# arduino_adapter_2a.net
KiCad netlist of a schematic drawn in EAGLE
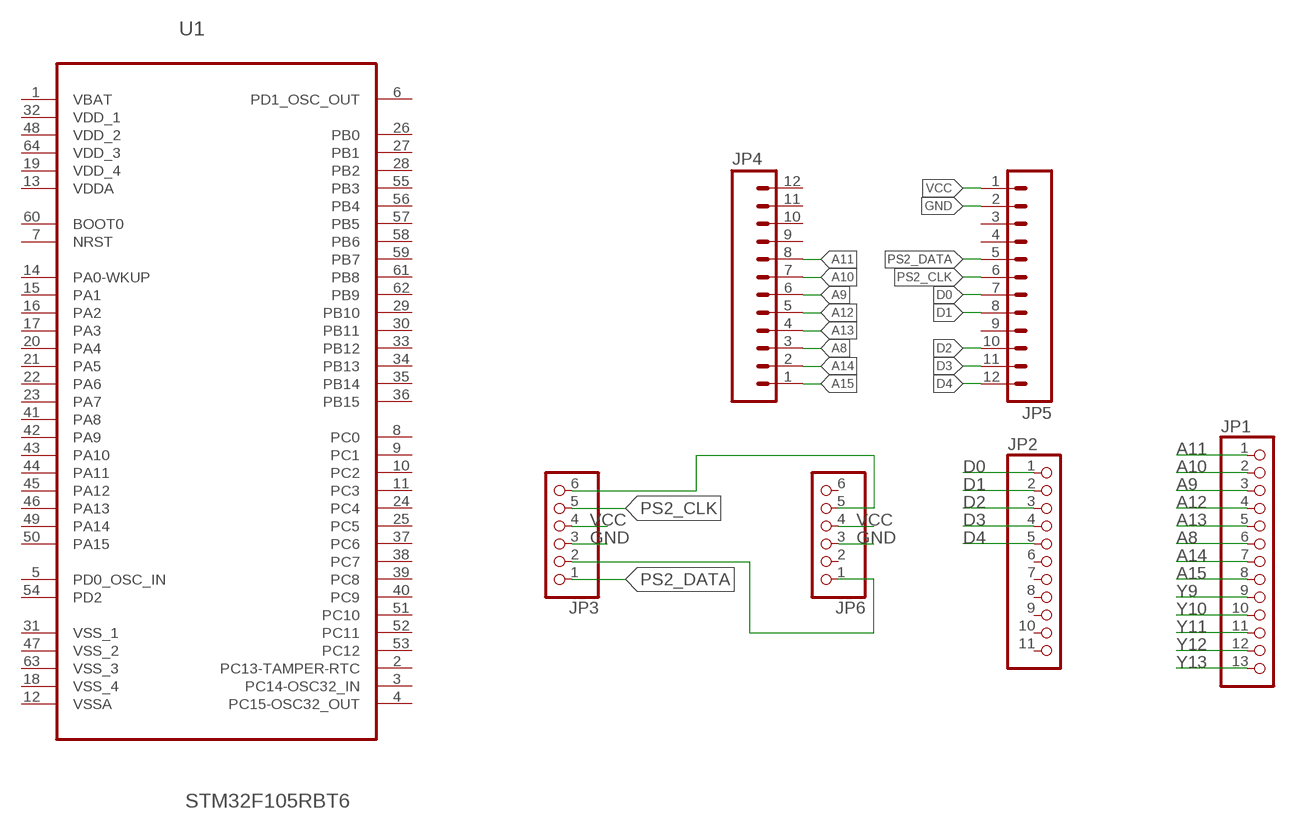
[diagram p0: schematic, sheet 1]

(export (version "E")
  (design (tool "Eeschema 10.0.6"))
  (components
    (comp (ref "JP1")
      (value "PINHD-1X13")
      (footprint "eagle-import:1X13")
      (libsource (lib "eagle-import") (part "PINHD-1X13"))
    )
    (comp (ref "JP2")
      (value "PINHD-1X11")
      (footprint "eagle-import:1X11")
      (libsource (lib "eagle-import") (part "PINHD-1X11"))
    )
    (comp (ref "JP3")
      (value "PINHD-1X6")
      (footprint "eagle-import:1X06")
      (libsource (lib "eagle-import") (part "PINHD-1X6"))
    )
    (comp (ref "JP4")
      (value "M12PTH")
      (footprint "eagle-import:1X12")
      (libsource (lib "eagle-import") (part "M12PTH"))
    )
    (comp (ref "JP5")
      (value "M12PTH")
      (footprint "eagle-import:1X12")
      (libsource (lib "eagle-import") (part "M12PTH"))
    )
    (comp (ref "JP6")
      (value "PINHD-1X6")
      (footprint "eagle-import:1X06")
      (libsource (lib "eagle-import") (part "PINHD-1X6"))
    )
    (comp (ref "U1")
      (value "STM32F105RBT6")
      (footprint "eagle-import:QFP50P1200X1200X160-64N")
      (libsource (lib "eagle-import") (part "STM32F105RBT6"))
    )
  )
  (nets
    (net (code "1") (name "/VBAT") (class "Default")
      (node (ref "U1") (pin "1") (pinfunction "VBAT_1") (pintype "power_in"))
    )
    (net (code "2") (name "/VDDA") (class "Default")
      (node (ref "U1") (pin "13") (pinfunction "VDDA_13") (pintype "power_in"))
    )
    (net (code "3") (name "/VDD_1") (class "Default")
      (node (ref "U1") (pin "32") (pinfunction "VDD_1_32") (pintype "power_in"))
    )
    (net (code "4") (name "/VDD_2") (class "Default")
      (node (ref "U1") (pin "48") (pinfunction "VDD_2_48") (pintype "power_in"))
    )
    (net (code "5") (name "/VDD_3") (class "Default")
      (node (ref "U1") (pin "64") (pinfunction "VDD_3_64") (pintype "power_in"))
    )
    (net (code "6") (name "/VDD_4") (class "Default")
      (node (ref "U1") (pin "19") (pinfunction "VDD_4_19") (pintype "power_in"))
    )
    (net (code "7") (name "/VSSA") (class "Default")
      (node (ref "U1") (pin "12") (pinfunction "VSSA_12") (pintype "power_in"))
    )
    (net (code "8") (name "/VSS_1") (class "Default")
      (node (ref "U1") (pin "31") (pinfunction "VSS_1_31") (pintype "power_in"))
    )
    (net (code "9") (name "/VSS_2") (class "Default")
      (node (ref "U1") (pin "47") (pinfunction "VSS_2_47") (pintype "power_in"))
    )
    (net (code "10") (name "/VSS_3") (class "Default")
      (node (ref "U1") (pin "63") (pinfunction "VSS_3_63") (pintype "power_in"))
    )
    (net (code "11") (name "/VSS_4") (class "Default")
      (node (ref "U1") (pin "18") (pinfunction "VSS_4_18") (pintype "power_in"))
    )
    (net (code "12") (name "/Y9") (class "Default")
      (node (ref "JP1") (pin "9") (pinfunction "9_9") (pintype "passive"))
    )
    (net (code "13") (name "/Y10") (class "Default")
      (node (ref "JP1") (pin "10") (pinfunction "10_10") (pintype "passive"))
    )
    (net (code "14") (name "/Y11") (class "Default")
      (node (ref "JP1") (pin "11") (pinfunction "11_11") (pintype "passive"))
    )
    (net (code "15") (name "/Y12") (class "Default")
      (node (ref "JP1") (pin "12") (pinfunction "12_12") (pintype "passive"))
    )
    (net (code "16") (name "/Y13") (class "Default")
      (node (ref "JP1") (pin "13") (pinfunction "13_13") (pintype "passive"))
    )
    (net (code "17") (name "A8") (class "Default")
      (node (ref "JP1") (pin "6") (pinfunction "6_6") (pintype "passive"))
      (node (ref "JP4") (pin "3") (pinfunction "3_3") (pintype "passive"))
    )
    (net (code "18") (name "A9") (class "Default")
      (node (ref "JP1") (pin "3") (pinfunction "3_3") (pintype "passive"))
      (node (ref "JP4") (pin "6") (pinfunction "6_6") (pintype "passive"))
    )
    (net (code "19") (name "A10") (class "Default")
      (node (ref "JP1") (pin "2") (pinfunction "2_2") (pintype "passive"))
      (node (ref "JP4") (pin "7") (pinfunction "7_7") (pintype "passive"))
    )
    (net (code "20") (name "A11") (class "Default")
      (node (ref "JP1") (pin "1") (pinfunction "1_1") (pintype "passive"))
      (node (ref "JP4") (pin "8") (pinfunction "8_8") (pintype "passive"))
    )
    (net (code "21") (name "A12") (class "Default")
      (node (ref "JP1") (pin "4") (pinfunction "4_4") (pintype "passive"))
      (node (ref "JP4") (pin "5") (pinfunction "5_5") (pintype "passive"))
    )
    (net (code "22") (name "A13") (class "Default")
      (node (ref "JP1") (pin "5") (pinfunction "5_5") (pintype "passive"))
      (node (ref "JP4") (pin "4") (pinfunction "4_4") (pintype "passive"))
    )
    (net (code "23") (name "A14") (class "Default")
      (node (ref "JP1") (pin "7") (pinfunction "7_7") (pintype "passive"))
      (node (ref "JP4") (pin "2") (pinfunction "2_2") (pintype "passive"))
    )
    (net (code "24") (name "A15") (class "Default")
      (node (ref "JP1") (pin "8") (pinfunction "8_8") (pintype "passive"))
      (node (ref "JP4") (pin "1") (pinfunction "1_1") (pintype "passive"))
    )
    (net (code "25") (name "D0") (class "Default")
      (node (ref "JP2") (pin "1") (pinfunction "1_1") (pintype "passive"))
      (node (ref "JP5") (pin "7") (pinfunction "7_7") (pintype "passive"))
    )
    (net (code "26") (name "D1") (class "Default")
      (node (ref "JP2") (pin "2") (pinfunction "2_2") (pintype "passive"))
      (node (ref "JP5") (pin "8") (pinfunction "8_8") (pintype "passive"))
    )
    (net (code "27") (name "D2") (class "Default")
      (node (ref "JP2") (pin "3") (pinfunction "3_3") (pintype "passive"))
      (node (ref "JP5") (pin "10") (pinfunction "10_10") (pintype "passive"))
    )
    (net (code "28") (name "D3") (class "Default")
      (node (ref "JP2") (pin "4") (pinfunction "4_4") (pintype "passive"))
      (node (ref "JP5") (pin "11") (pinfunction "11_11") (pintype "passive"))
    )
    (net (code "29") (name "D4") (class "Default")
      (node (ref "JP2") (pin "5") (pinfunction "5_5") (pintype "passive"))
      (node (ref "JP5") (pin "12") (pinfunction "12_12") (pintype "passive"))
    )
    (net (code "30") (name "GND") (class "Default")
      (node (ref "JP3") (pin "3") (pinfunction "3_3") (pintype "passive"))
      (node (ref "JP5") (pin "2") (pinfunction "2_2") (pintype "passive"))
      (node (ref "JP6") (pin "3") (pinfunction "3_3") (pintype "passive"))
    )
    (net (code "31") (name "Net-(JP3-Pad2)") (class "Default")
      (node (ref "JP3") (pin "2") (pinfunction "2_2") (pintype "passive"))
      (node (ref "JP6") (pin "1") (pinfunction "1_1") (pintype "passive"))
    )
    (net (code "32") (name "Net-(JP3-Pad6)") (class "Default")
      (node (ref "JP3") (pin "6") (pinfunction "6_6") (pintype "passive"))
      (node (ref "JP6") (pin "5") (pinfunction "5_5") (pintype "passive"))
    )
    (net (code "33") (name "PS2_CLK") (class "Default")
      (node (ref "JP3") (pin "5") (pinfunction "5_5") (pintype "passive"))
      (node (ref "JP5") (pin "6") (pinfunction "6_6") (pintype "passive"))
    )
    (net (code "34") (name "PS2_DATA") (class "Default")
      (node (ref "JP3") (pin "1") (pinfunction "1_1") (pintype "passive"))
      (node (ref "JP5") (pin "5") (pinfunction "5_5") (pintype "passive"))
    )
    (net (code "35") (name "VCC") (class "Default")
      (node (ref "JP3") (pin "4") (pinfunction "4_4") (pintype "passive"))
      (node (ref "JP5") (pin "1") (pinfunction "1_1") (pintype "passive"))
      (node (ref "JP6") (pin "4") (pinfunction "4_4") (pintype "passive"))
    )
    (net (code "36") (name "unconnected-(JP2-Pad6)") (class "Default")
      (node (ref "JP2") (pin "6") (pinfunction "6_6") (pintype "passive"))
    )
    (net (code "37") (name "unconnected-(JP2-Pad7)") (class "Default")
      (node (ref "JP2") (pin "7") (pinfunction "7_7") (pintype "passive"))
    )
    (net (code "38") (name "unconnected-(JP2-Pad8)") (class "Default")
      (node (ref "JP2") (pin "8") (pinfunction "8_8") (pintype "passive"))
    )
    (net (code "39") (name "unconnected-(JP2-Pad9)") (class "Default")
      (node (ref "JP2") (pin "9") (pinfunction "9_9") (pintype "passive"))
    )
    (net (code "40") (name "unconnected-(JP2-Pad10)") (class "Default")
      (node (ref "JP2") (pin "10") (pinfunction "10_10") (pintype "passive"))
    )
    (net (code "41") (name "unconnected-(JP2-Pad11)") (class "Default")
      (node (ref "JP2") (pin "11") (pinfunction "11_11") (pintype "passive"))
    )
    (net (code "42") (name "unconnected-(JP4-Pad9)") (class "Default")
      (node (ref "JP4") (pin "9") (pinfunction "9_9") (pintype "passive"))
    )
    (net (code "43") (name "unconnected-(JP4-Pad10)") (class "Default")
      (node (ref "JP4") (pin "10") (pinfunction "10_10") (pintype "passive"))
    )
    (net (code "44") (name "unconnected-(JP4-Pad11)") (class "Default")
      (node (ref "JP4") (pin "11") (pinfunction "11_11") (pintype "passive"))
    )
    (net (code "45") (name "unconnected-(JP4-Pad12)") (class "Default")
      (node (ref "JP4") (pin "12") (pinfunction "12_12") (pintype "passive"))
    )
    (net (code "46") (name "unconnected-(JP5-Pad3)") (class "Default")
      (node (ref "JP5") (pin "3") (pinfunction "3_3") (pintype "passive"))
    )
    (net (code "47") (name "unconnected-(JP5-Pad4)") (class "Default")
      (node (ref "JP5") (pin "4") (pinfunction "4_4") (pintype "passive"))
    )
    (net (code "48") (name "unconnected-(JP5-Pad9)") (class "Default")
      (node (ref "JP5") (pin "9") (pinfunction "9_9") (pintype "passive"))
    )
    (net (code "49") (name "unconnected-(JP6-Pad2)") (class "Default")
      (node (ref "JP6") (pin "2") (pinfunction "2_2") (pintype "passive"))
    )
    (net (code "50") (name "unconnected-(JP6-Pad6)") (class "Default")
      (node (ref "JP6") (pin "6") (pinfunction "6_6") (pintype "passive"))
    )
    (net (code "51") (name "unconnected-(U1-BOOT0-Pad60)") (class "Default")
      (node (ref "U1") (pin "60") (pinfunction "BOOT0_60") (pintype "input"))
    )
    (net (code "52") (name "unconnected-(U1-NRST-Pad7)") (class "Default")
      (node (ref "U1") (pin "7") (pinfunction "NRST_7") (pintype "bidirectional"))
    )
    (net (code "53") (name "unconnected-(U1-PA0-WKUP-Pad14)") (class "Default")
      (node (ref "U1") (pin "14") (pinfunction "PA0-WKUP_14") (pintype "bidirectional"))
    )
    (net (code "54") (name "unconnected-(U1-PA1-Pad15)") (class "Default")
      (node (ref "U1") (pin "15") (pinfunction "PA1_15") (pintype "bidirectional"))
    )
    (net (code "55") (name "unconnected-(U1-PA2-Pad16)") (class "Default")
      (node (ref "U1") (pin "16") (pinfunction "PA2_16") (pintype "bidirectional"))
    )
    (net (code "56") (name "unconnected-(U1-PA3-Pad17)") (class "Default")
      (node (ref "U1") (pin "17") (pinfunction "PA3_17") (pintype "bidirectional"))
    )
    (net (code "57") (name "unconnected-(U1-PA4-Pad20)") (class "Default")
      (node (ref "U1") (pin "20") (pinfunction "PA4_20") (pintype "bidirectional"))
    )
    (net (code "58") (name "unconnected-(U1-PA5-Pad21)") (class "Default")
      (node (ref "U1") (pin "21") (pinfunction "PA5_21") (pintype "bidirectional"))
    )
    (net (code "59") (name "unconnected-(U1-PA6-Pad22)") (class "Default")
      (node (ref "U1") (pin "22") (pinfunction "PA6_22") (pintype "bidirectional"))
    )
    (net (code "60") (name "unconnected-(U1-PA7-Pad23)") (class "Default")
      (node (ref "U1") (pin "23") (pinfunction "PA7_23") (pintype "bidirectional"))
    )
    (net (code "61") (name "unconnected-(U1-PA8-Pad41)") (class "Default")
      (node (ref "U1") (pin "41") (pinfunction "PA8_41") (pintype "bidirectional"))
    )
    (net (code "62") (name "unconnected-(U1-PA9-Pad42)") (class "Default")
      (node (ref "U1") (pin "42") (pinfunction "PA9_42") (pintype "bidirectional"))
    )
    (net (code "63") (name "unconnected-(U1-PA10-Pad43)") (class "Default")
      (node (ref "U1") (pin "43") (pinfunction "PA10_43") (pintype "bidirectional"))
    )
    (net (code "64") (name "unconnected-(U1-PA11-Pad44)") (class "Default")
      (node (ref "U1") (pin "44") (pinfunction "PA11_44") (pintype "bidirectional"))
    )
    (net (code "65") (name "unconnected-(U1-PA12-Pad45)") (class "Default")
      (node (ref "U1") (pin "45") (pinfunction "PA12_45") (pintype "bidirectional"))
    )
    (net (code "66") (name "unconnected-(U1-PA13-Pad46)") (class "Default")
      (node (ref "U1") (pin "46") (pinfunction "PA13_46") (pintype "bidirectional"))
    )
    (net (code "67") (name "unconnected-(U1-PA14-Pad49)") (class "Default")
      (node (ref "U1") (pin "49") (pinfunction "PA14_49") (pintype "bidirectional"))
    )
    (net (code "68") (name "unconnected-(U1-PA15-Pad50)") (class "Default")
      (node (ref "U1") (pin "50") (pinfunction "PA15_50") (pintype "bidirectional"))
    )
    (net (code "69") (name "unconnected-(U1-PB0-Pad26)") (class "Default")
      (node (ref "U1") (pin "26") (pinfunction "PB0_26") (pintype "bidirectional"))
    )
    (net (code "70") (name "unconnected-(U1-PB1-Pad27)") (class "Default")
      (node (ref "U1") (pin "27") (pinfunction "PB1_27") (pintype "bidirectional"))
    )
    (net (code "71") (name "unconnected-(U1-PB2-Pad28)") (class "Default")
      (node (ref "U1") (pin "28") (pinfunction "PB2_28") (pintype "bidirectional"))
    )
    (net (code "72") (name "unconnected-(U1-PB3-Pad55)") (class "Default")
      (node (ref "U1") (pin "55") (pinfunction "PB3_55") (pintype "bidirectional"))
    )
    (net (code "73") (name "unconnected-(U1-PB4-Pad56)") (class "Default")
      (node (ref "U1") (pin "56") (pinfunction "PB4_56") (pintype "bidirectional"))
    )
    (net (code "74") (name "unconnected-(U1-PB5-Pad57)") (class "Default")
      (node (ref "U1") (pin "57") (pinfunction "PB5_57") (pintype "bidirectional"))
    )
    (net (code "75") (name "unconnected-(U1-PB6-Pad58)") (class "Default")
      (node (ref "U1") (pin "58") (pinfunction "PB6_58") (pintype "bidirectional"))
    )
    (net (code "76") (name "unconnected-(U1-PB7-Pad59)") (class "Default")
      (node (ref "U1") (pin "59") (pinfunction "PB7_59") (pintype "bidirectional"))
    )
    (net (code "77") (name "unconnected-(U1-PB8-Pad61)") (class "Default")
      (node (ref "U1") (pin "61") (pinfunction "PB8_61") (pintype "bidirectional"))
    )
    (net (code "78") (name "unconnected-(U1-PB9-Pad62)") (class "Default")
      (node (ref "U1") (pin "62") (pinfunction "PB9_62") (pintype "bidirectional"))
    )
    (net (code "79") (name "unconnected-(U1-PB10-Pad29)") (class "Default")
      (node (ref "U1") (pin "29") (pinfunction "PB10_29") (pintype "bidirectional"))
    )
    (net (code "80") (name "unconnected-(U1-PB11-Pad30)") (class "Default")
      (node (ref "U1") (pin "30") (pinfunction "PB11_30") (pintype "bidirectional"))
    )
    (net (code "81") (name "unconnected-(U1-PB12-Pad33)") (class "Default")
      (node (ref "U1") (pin "33") (pinfunction "PB12_33") (pintype "bidirectional"))
    )
    (net (code "82") (name "unconnected-(U1-PB13-Pad34)") (class "Default")
      (node (ref "U1") (pin "34") (pinfunction "PB13_34") (pintype "bidirectional"))
    )
    (net (code "83") (name "unconnected-(U1-PB14-Pad35)") (class "Default")
      (node (ref "U1") (pin "35") (pinfunction "PB14_35") (pintype "bidirectional"))
    )
    (net (code "84") (name "unconnected-(U1-PB15-Pad36)") (class "Default")
      (node (ref "U1") (pin "36") (pinfunction "PB15_36") (pintype "bidirectional"))
    )
    (net (code "85") (name "unconnected-(U1-PC0-Pad8)") (class "Default")
      (node (ref "U1") (pin "8") (pinfunction "PC0_8") (pintype "bidirectional"))
    )
    (net (code "86") (name "unconnected-(U1-PC1-Pad9)") (class "Default")
      (node (ref "U1") (pin "9") (pinfunction "PC1_9") (pintype "bidirectional"))
    )
    (net (code "87") (name "unconnected-(U1-PC2-Pad10)") (class "Default")
      (node (ref "U1") (pin "10") (pinfunction "PC2_10") (pintype "bidirectional"))
    )
    (net (code "88") (name "unconnected-(U1-PC3-Pad11)") (class "Default")
      (node (ref "U1") (pin "11") (pinfunction "PC3_11") (pintype "bidirectional"))
    )
    (net (code "89") (name "unconnected-(U1-PC4-Pad24)") (class "Default")
      (node (ref "U1") (pin "24") (pinfunction "PC4_24") (pintype "bidirectional"))
    )
    (net (code "90") (name "unconnected-(U1-PC5-Pad25)") (class "Default")
      (node (ref "U1") (pin "25") (pinfunction "PC5_25") (pintype "bidirectional"))
    )
    (net (code "91") (name "unconnected-(U1-PC6-Pad37)") (class "Default")
      (node (ref "U1") (pin "37") (pinfunction "PC6_37") (pintype "bidirectional"))
    )
    (net (code "92") (name "unconnected-(U1-PC7-Pad38)") (class "Default")
      (node (ref "U1") (pin "38") (pinfunction "PC7_38") (pintype "bidirectional"))
    )
    (net (code "93") (name "unconnected-(U1-PC8-Pad39)") (class "Default")
      (node (ref "U1") (pin "39") (pinfunction "PC8_39") (pintype "bidirectional"))
    )
    (net (code "94") (name "unconnected-(U1-PC9-Pad40)") (class "Default")
      (node (ref "U1") (pin "40") (pinfunction "PC9_40") (pintype "bidirectional"))
    )
    (net (code "95") (name "unconnected-(U1-PC10-Pad51)") (class "Default")
      (node (ref "U1") (pin "51") (pinfunction "PC10_51") (pintype "bidirectional"))
    )
    (net (code "96") (name "unconnected-(U1-PC11-Pad52)") (class "Default")
      (node (ref "U1") (pin "52") (pinfunction "PC11_52") (pintype "bidirectional"))
    )
    (net (code "97") (name "unconnected-(U1-PC12-Pad53)") (class "Default")
      (node (ref "U1") (pin "53") (pinfunction "PC12_53") (pintype "bidirectional"))
    )
    (net (code "98") (name "unconnected-(U1-PC13-TAMPER-RTC-Pad2)") (class "Default")
      (node (ref "U1") (pin "2") (pinfunction "PC13-TAMPER-RTC_2") (pintype "bidirectional"))
    )
    (net (code "99") (name "unconnected-(U1-PC14-OSC32_IN-Pad3)") (class "Default")
      (node (ref "U1") (pin "3") (pinfunction "PC14-OSC32_IN_3") (pintype "bidirectional"))
    )
    (net (code "100") (name "unconnected-(U1-PC15-OSC32_OUT-Pad4)") (class "Default")
      (node (ref "U1") (pin "4") (pinfunction "PC15-OSC32_OUT_4") (pintype "bidirectional"))
    )
    (net (code "101") (name "unconnected-(U1-PD0_OSC_IN-Pad5)") (class "Default")
      (node (ref "U1") (pin "5") (pinfunction "PD0_OSC_IN_5") (pintype "bidirectional"))
    )
    (net (code "102") (name "unconnected-(U1-PD1_OSC_OUT-Pad6)") (class "Default")
      (node (ref "U1") (pin "6") (pinfunction "PD1_OSC_OUT_6") (pintype "bidirectional"))
    )
    (net (code "103") (name "unconnected-(U1-PD2-Pad54)") (class "Default")
      (node (ref "U1") (pin "54") (pinfunction "PD2_54") (pintype "bidirectional"))
    )
  )
)
